# stm_board_f407.net
KiCad netlist of a schematic drawn in EAGLE
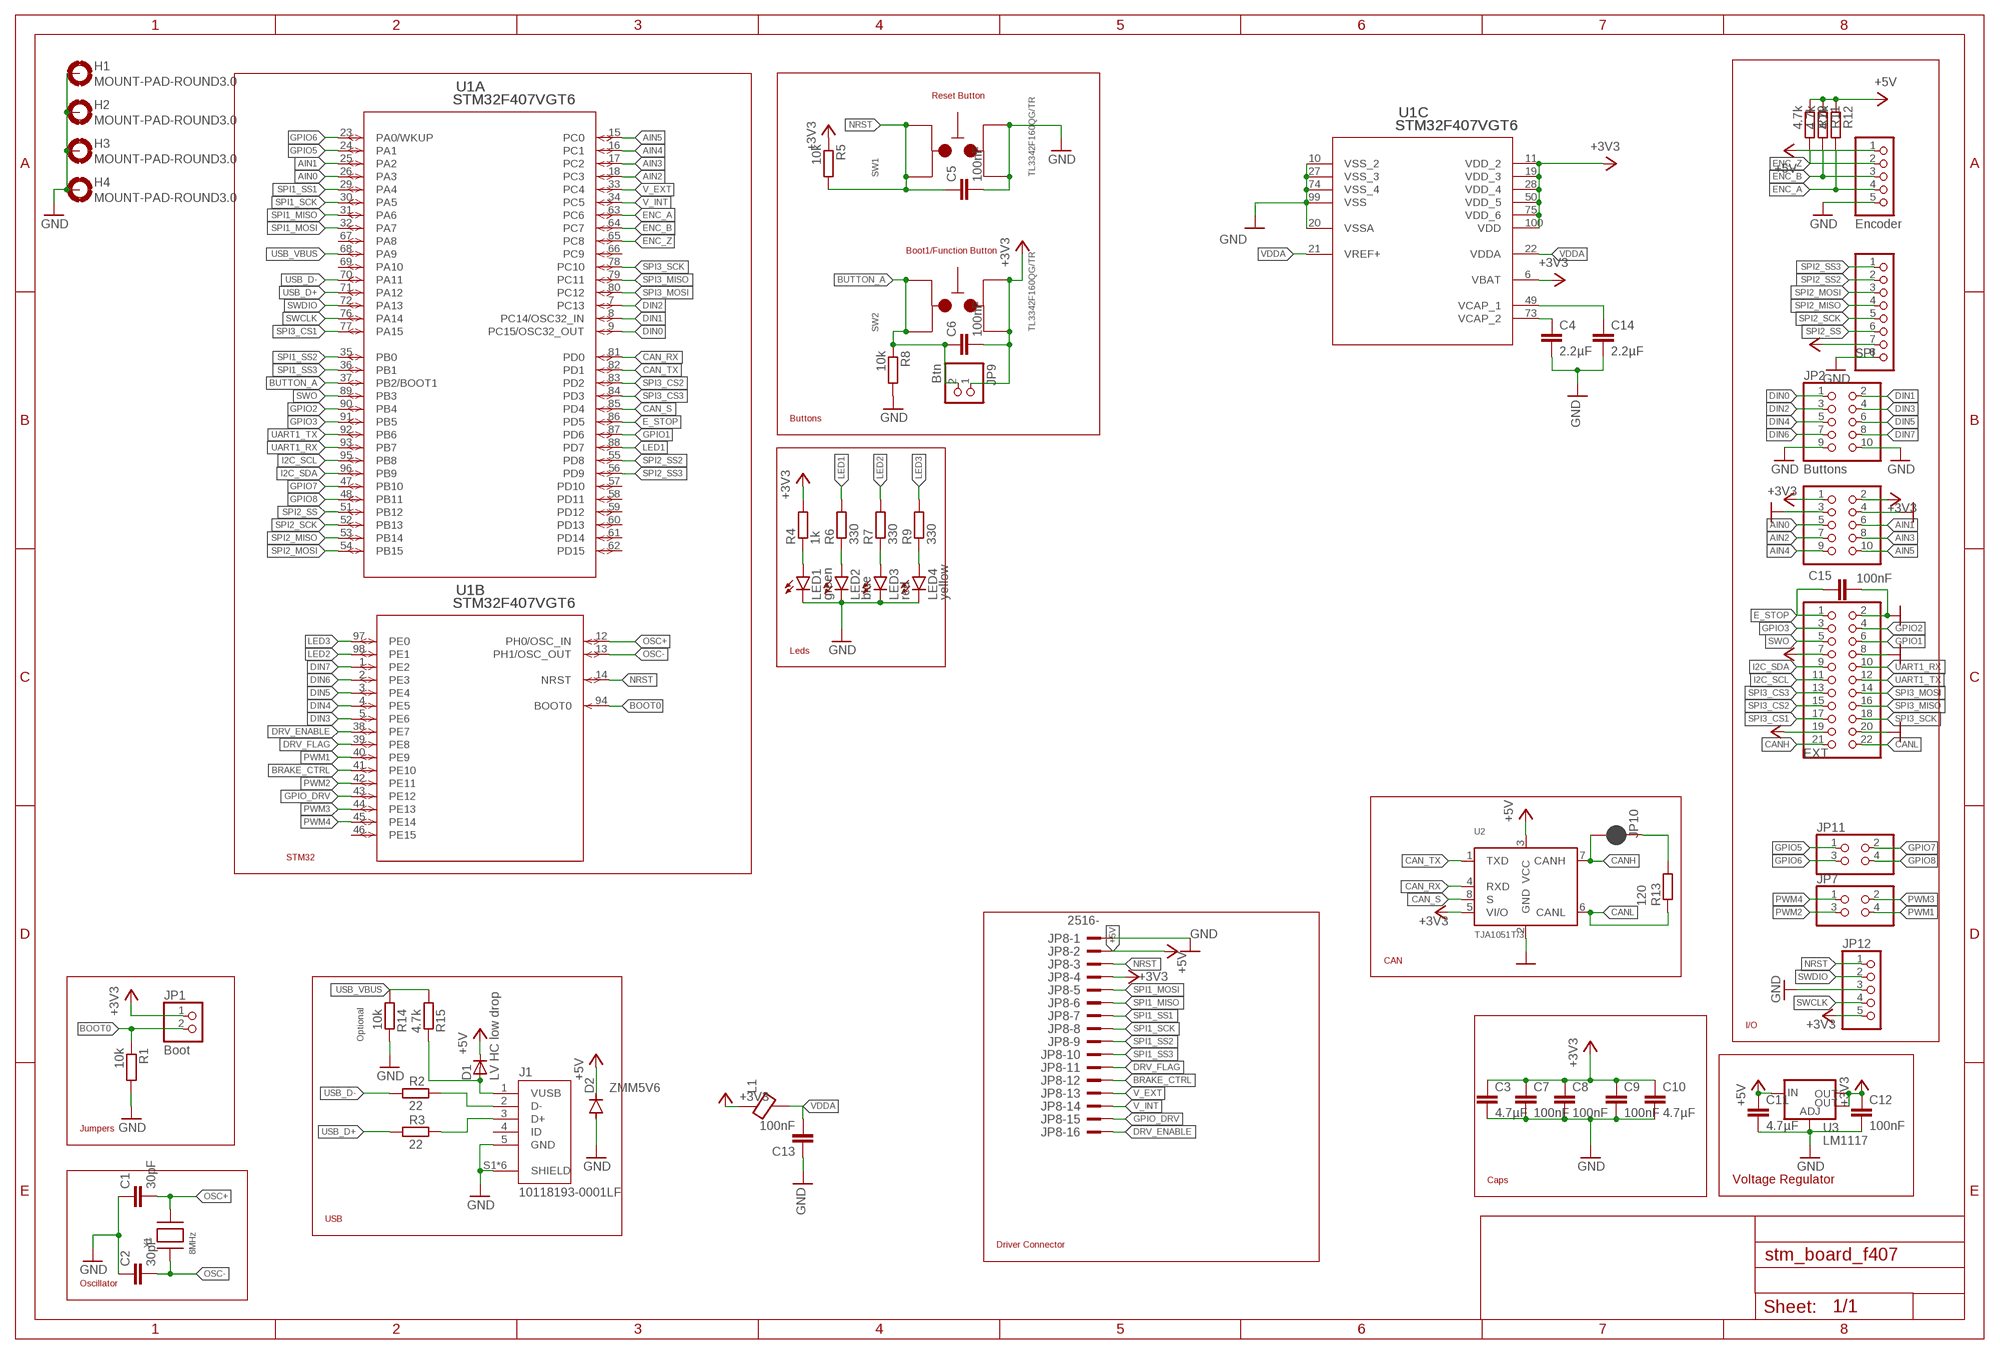
[diagram p0: schematic, sheet 1]

(export (version "E")
  (design (tool "Eeschema 10.0.6"))
  (components
    (comp (ref "C1")
      (value "30pF")
      (footprint "eagle-import:C0603")
      (libsource (lib "eagle-import") (part "C-EUC0603"))
    )
    (comp (ref "C2")
      (value "30pF")
      (footprint "eagle-import:C0603")
      (libsource (lib "eagle-import") (part "C-EUC0603"))
    )
    (comp (ref "C3")
      (value "4.7µF")
      (footprint "eagle-import:C0805")
      (libsource (lib "eagle-import") (part "C-EUC0805"))
    )
    (comp (ref "C4")
      (value "2.2µF")
      (footprint "eagle-import:C0603")
      (libsource (lib "eagle-import") (part "C-EUC0603"))
    )
    (comp (ref "C5")
      (value "100nF")
      (footprint "eagle-import:C0603")
      (libsource (lib "eagle-import") (part "C-EUC0603"))
    )
    (comp (ref "C6")
      (value "100nF")
      (footprint "eagle-import:C0603")
      (libsource (lib "eagle-import") (part "C-EUC0603"))
    )
    (comp (ref "C7")
      (value "100nF")
      (footprint "eagle-import:C0603")
      (libsource (lib "eagle-import") (part "C-EUC0603"))
    )
    (comp (ref "C8")
      (value "100nF")
      (footprint "eagle-import:C0603")
      (libsource (lib "eagle-import") (part "C-EUC0603"))
    )
    (comp (ref "C9")
      (value "100nF")
      (footprint "eagle-import:C0603")
      (libsource (lib "eagle-import") (part "C-EUC0603"))
    )
    (comp (ref "C10")
      (value "4.7µF")
      (footprint "eagle-import:C0805")
      (libsource (lib "eagle-import") (part "C-EUC0805"))
    )
    (comp (ref "C11")
      (value "4.7µF")
      (footprint "eagle-import:C0805")
      (libsource (lib "eagle-import") (part "C-EUC0805"))
    )
    (comp (ref "C12")
      (value "100nF")
      (footprint "eagle-import:C0603")
      (libsource (lib "eagle-import") (part "C-EUC0603"))
    )
    (comp (ref "C13")
      (value "100nF")
      (footprint "eagle-import:C0603")
      (libsource (lib "eagle-import") (part "C-EUC0603"))
    )
    (comp (ref "C14")
      (value "2.2µF")
      (footprint "eagle-import:C0603")
      (libsource (lib "eagle-import") (part "C-EUC0603"))
    )
    (comp (ref "C15")
      (value "100nF")
      (footprint "eagle-import:C0603")
      (libsource (lib "eagle-import") (part "C-EUC0603"))
    )
    (comp (ref "D1")
      (value "LV HC low drop")
      (footprint "eagle-import:SMADIODE")
      (libsource (lib "eagle-import") (part "DIODESMA"))
    )
    (comp (ref "D2")
      (value "ZMM5V6")
      (footprint "eagle-import:MINIMELF")
      (libsource (lib "eagle-import") (part "DIODE-MINIMELF"))
    )
    (comp (ref "H1")
      (value "MOUNT-PAD-ROUND3.0")
      (footprint "eagle-import:3,0-PAD")
      (libsource (lib "eagle-import") (part "MOUNT-PAD-ROUND3.0"))
    )
    (comp (ref "H2")
      (value "MOUNT-PAD-ROUND3.0")
      (footprint "eagle-import:3,0-PAD")
      (libsource (lib "eagle-import") (part "MOUNT-PAD-ROUND3.0"))
    )
    (comp (ref "H3")
      (value "MOUNT-PAD-ROUND3.0")
      (footprint "eagle-import:3,0-PAD")
      (libsource (lib "eagle-import") (part "MOUNT-PAD-ROUND3.0"))
    )
    (comp (ref "H4")
      (value "MOUNT-PAD-ROUND3.0")
      (footprint "eagle-import:3,0-PAD")
      (libsource (lib "eagle-import") (part "MOUNT-PAD-ROUND3.0"))
    )
    (comp (ref "J1")
      (value "10118193-0001LF")
      (footprint "eagle-import:FCI_10118193-0001LF")
      (fields (field (name "MF") "Amphenol ICC"))
      (libsource (lib "eagle-import") (part "10118193-0001LF"))
    )
    (comp (ref "JP1")
      (value "Boot")
      (footprint "eagle-import:1X02")
      (libsource (lib "eagle-import") (part "PINHD-1X2"))
    )
    (comp (ref "JP2")
      (value "Buttons")
      (footprint "eagle-import:2X05")
      (libsource (lib "eagle-import") (part "PINHD-2X5"))
    )
    (comp (ref "JP3")
      (value "Analog")
      (footprint "eagle-import:2X05")
      (libsource (lib "eagle-import") (part "PINHD-2X5"))
    )
    (comp (ref "JP4")
      (value "EXT")
      (footprint "eagle-import:2X11")
      (libsource (lib "eagle-import") (part "PINHD-2X11"))
    )
    (comp (ref "JP5")
      (value "Encoder")
      (footprint "eagle-import:1X05")
      (libsource (lib "eagle-import") (part "PINHD-1X5"))
    )
    (comp (ref "JP6")
      (value "SPI")
      (footprint "eagle-import:1X08")
      (libsource (lib "eagle-import") (part "PINHD-1X8"))
    )
    (comp (ref "JP7")
      (value "PINHD-2X2")
      (footprint "eagle-import:2X02")
      (libsource (lib "eagle-import") (part "PINHD-2X2"))
    )
    (comp (ref "JP8")
      (value "2516-")
      (footprint "eagle-import:PAK100_2500-16")
      (libsource (lib "eagle-import") (part "2516-"))
    )
    (comp (ref "JP9")
      (value "Btn")
      (footprint "eagle-import:1X02")
      (libsource (lib "eagle-import") (part "PINHD-1X2"))
    )
    (comp (ref "JP10")
      (value "JUMPER-SMT_2_NC_PASTE_NO-SILK")
      (footprint "eagle-import:SMT-JUMPER_2_NC_PASTE_NO-SILK")
      (libsource (lib "eagle-import") (part "JUMPER-SMT_2_NC_PASTE_NO-SILK"))
    )
    (comp (ref "JP11")
      (value "PINHD-2X2")
      (footprint "eagle-import:2X02")
      (libsource (lib "eagle-import") (part "PINHD-2X2"))
    )
    (comp (ref "JP12")
      (value "PINHD-1X5")
      (footprint "eagle-import:1X05")
      (libsource (lib "eagle-import") (part "PINHD-1X5"))
    )
    (comp (ref "L1")
      (value "GZ2012D601TF")
      (footprint "eagle-import:BLM21PG331SN1D")
      (fields
        (field (name "DIGIKEY_PART_NUMBER") "490-5988-2-ND")
        (field (name "MANUFACTURER") "Murata Electronics North America")
        (field (name "MPN") "BLM21PG331SN1D")
        (field (name "CREATED_BY") "PCBLayout.com")
      )
      (libsource (lib "eagle-import") (part "BLM21PG331SN1D"))
    )
    (comp (ref "LED1")
      (value "green")
      (footprint "eagle-import:SML0805")
      (libsource (lib "eagle-import") (part "LEDSML0805"))
    )
    (comp (ref "LED2")
      (value "blue")
      (footprint "eagle-import:SML0805")
      (libsource (lib "eagle-import") (part "LEDSML0805"))
    )
    (comp (ref "LED3")
      (value "red")
      (footprint "eagle-import:SML0805")
      (libsource (lib "eagle-import") (part "LEDSML0805"))
    )
    (comp (ref "LED4")
      (value "yellow")
      (footprint "eagle-import:SML0805")
      (libsource (lib "eagle-import") (part "LEDSML0805"))
    )
    (comp (ref "R1")
      (value "10k")
      (footprint "eagle-import:R0603")
      (libsource (lib "eagle-import") (part "R-EU_R0603"))
    )
    (comp (ref "R2")
      (value "22")
      (footprint "eagle-import:R0603")
      (libsource (lib "eagle-import") (part "R-EU_R0603"))
    )
    (comp (ref "R3")
      (value "22")
      (footprint "eagle-import:R0603")
      (libsource (lib "eagle-import") (part "R-EU_R0603"))
    )
    (comp (ref "R4")
      (value "1k")
      (footprint "eagle-import:R0603")
      (libsource (lib "eagle-import") (part "R-EU_R0603"))
    )
    (comp (ref "R5")
      (value "10k")
      (footprint "eagle-import:R0603")
      (libsource (lib "eagle-import") (part "R-EU_R0603"))
    )
    (comp (ref "R6")
      (value "330")
      (footprint "eagle-import:R0603")
      (libsource (lib "eagle-import") (part "R-EU_R0603"))
    )
    (comp (ref "R7")
      (value "330")
      (footprint "eagle-import:R0603")
      (libsource (lib "eagle-import") (part "R-EU_R0603"))
    )
    (comp (ref "R8")
      (value "10k")
      (footprint "eagle-import:R0603")
      (libsource (lib "eagle-import") (part "R-EU_R0603"))
    )
    (comp (ref "R9")
      (value "330")
      (footprint "eagle-import:R0603")
      (libsource (lib "eagle-import") (part "R-EU_R0603"))
    )
    (comp (ref "R10")
      (value "4.7k")
      (footprint "eagle-import:R0603")
      (libsource (lib "eagle-import") (part "R-EU_R0603"))
    )
    (comp (ref "R11")
      (value "4.7k")
      (footprint "eagle-import:R0603")
      (libsource (lib "eagle-import") (part "R-EU_R0603"))
    )
    (comp (ref "R12")
      (value "4.7k")
      (footprint "eagle-import:R0603")
      (libsource (lib "eagle-import") (part "R-EU_R0603"))
    )
    (comp (ref "R13")
      (value "120")
      (footprint "eagle-import:R0603")
      (libsource (lib "eagle-import") (part "R-EU_R0603"))
    )
    (comp (ref "R14")
      (value "10k")
      (footprint "eagle-import:R0603")
      (libsource (lib "eagle-import") (part "R-EU_R0603"))
    )
    (comp (ref "R15")
      (value "4.7k")
      (footprint "eagle-import:R0603")
      (libsource (lib "eagle-import") (part "R-EU_R0603"))
    )
    (comp (ref "SW1")
      (value "TL3342F160QG/TR")
      (footprint "eagle-import:TL3342F160QG_TR")
      (fields
        (field (name "DIGI_KEY_PART_NUMBER") "EG2531CT-ND")
        (field (name "MANUFACTURER") "E-Switch")
        (field (name "CREATED_BY") "PCBLayout.com")
      )
      (libsource (lib "eagle-import") (part "TL3342F160QG/TR"))
    )
    (comp (ref "SW2")
      (value "TL3342F160QG/TR")
      (footprint "eagle-import:TL3342F160QG_TR")
      (fields
        (field (name "DIGI_KEY_PART_NUMBER") "EG2531CT-ND")
        (field (name "MANUFACTURER") "E-Switch")
        (field (name "CREATED_BY") "PCBLayout.com")
      )
      (libsource (lib "eagle-import") (part "TL3342F160QG/TR"))
    )
    (comp (ref "U1")
      (value "STM32F407VGT6")
      (footprint "eagle-import:LQFP100-14X14MM")
      (fields (field (name "COPYRIGHT") "Copyright (C) 2018 Accelerated Designs. All rights reserved"))
      (libsource (lib "eagle-import") (part "STM32F407VGT6"))
    )
    (comp (ref "U2")
      (value "TJA1051T/3")
      (footprint "eagle-import:SOT96-1")
      (fields (field (name "MF") "NXP Semiconductors"))
      (libsource (lib "eagle-import") (part "TJA1051T/3"))
    )
    (comp (ref "U3")
      (value "LM1117")
      (footprint "eagle-import:SOT223")
      (libsource (lib "eagle-import") (part "V_REG_LM1117SOT223"))
    )
    (comp (ref "X1")
      (value "8MHz")
      (footprint "eagle-import:NX5032")
      (libsource (lib "eagle-import") (part "XTALNX5032"))
    )
  )
  (nets
    (net (code "1") (name "+3V3") (class "Default")
      (node (ref "C10") (pin "1") (pinfunction "1_1") (pintype "passive"))
      (node (ref "C12") (pin "1") (pinfunction "1_1") (pintype "passive"))
      (node (ref "C3") (pin "1") (pinfunction "1_1") (pintype "passive"))
      (node (ref "C6") (pin "2") (pinfunction "2_2") (pintype "passive"))
      (node (ref "C7") (pin "1") (pinfunction "1_1") (pintype "passive"))
      (node (ref "C8") (pin "1") (pinfunction "1_1") (pintype "passive"))
      (node (ref "C9") (pin "1") (pinfunction "1_1") (pintype "passive"))
      (node (ref "JP1") (pin "1") (pinfunction "1_1") (pintype "passive"))
      (node (ref "JP12") (pin "5") (pinfunction "5_5") (pintype "passive"))
      (node (ref "JP3") (pin "1") (pinfunction "1_1") (pintype "passive"))
      (node (ref "JP3") (pin "2") (pinfunction "2_2") (pintype "passive"))
      (node (ref "JP4") (pin "7") (pinfunction "7_7") (pintype "passive"))
      (node (ref "JP6") (pin "7") (pinfunction "7_7") (pintype "passive"))
      (node (ref "JP8") (pin "4") (pinfunction "KL_4") (pintype "passive"))
      (node (ref "JP9") (pin "1") (pinfunction "1_1") (pintype "passive"))
      (node (ref "L1") (pin "1") (pinfunction "1_1") (pintype "passive"))
      (node (ref "R4") (pin "2") (pinfunction "2_2") (pintype "passive"))
      (node (ref "R5") (pin "1") (pinfunction "1_1") (pintype "passive"))
      (node (ref "SW2") (pin "1") (pinfunction "1_1") (pintype "passive"))
      (node (ref "SW2") (pin "2") (pinfunction "2_2") (pintype "passive"))
      (node (ref "U1") (pin "100") (pinfunction "VDD_100") (pintype "power_in"))
      (node (ref "U1") (pin "11") (pinfunction "VDD_2_11") (pintype "power_in"))
      (node (ref "U1") (pin "19") (pinfunction "VDD_3_19") (pintype "power_in"))
      (node (ref "U1") (pin "28") (pinfunction "VDD_4_28") (pintype "power_in"))
      (node (ref "U1") (pin "50") (pinfunction "VDD_5_50") (pintype "power_in"))
      (node (ref "U1") (pin "6") (pinfunction "VBAT_6") (pintype "power_in"))
      (node (ref "U1") (pin "75") (pinfunction "VDD_6_75") (pintype "power_in"))
      (node (ref "U2") (pin "5") (pinfunction "VI/O_5") (pintype "passive"))
      (node (ref "U3") (pin "2") (pinfunction "OUT_2") (pintype "output"))
      (node (ref "U3") (pin "4") (pinfunction "OUT_4") (pintype "output"))
    )
    (net (code "2") (name "+5V") (class "Default")
      (node (ref "C11") (pin "1") (pinfunction "1_1") (pintype "passive"))
      (node (ref "D1") (pin "C") (pinfunction "C_C") (pintype "passive"))
      (node (ref "D2") (pin "C") (pinfunction "C_C") (pintype "passive"))
      (node (ref "JP4") (pin "19") (pinfunction "19_19") (pintype "passive"))
      (node (ref "JP5") (pin "1") (pinfunction "1_1") (pintype "passive"))
      (node (ref "JP8") (pin "2") (pinfunction "KL_2") (pintype "passive"))
      (node (ref "R10") (pin "1") (pinfunction "1_1") (pintype "passive"))
      (node (ref "R11") (pin "1") (pinfunction "1_1") (pintype "passive"))
      (node (ref "R12") (pin "1") (pinfunction "1_1") (pintype "passive"))
      (node (ref "U2") (pin "3") (pinfunction "VCC_3") (pintype "bidirectional"))
      (node (ref "U3") (pin "3") (pinfunction "IN_3") (pintype "input"))
    )
    (net (code "3") (name "AIN0") (class "Default")
      (node (ref "JP3") (pin "5") (pinfunction "5_5") (pintype "passive"))
      (node (ref "U1") (pin "26") (pinfunction "PA3_26") (pintype "bidirectional"))
    )
    (net (code "4") (name "AIN1") (class "Default")
      (node (ref "JP3") (pin "6") (pinfunction "6_6") (pintype "passive"))
      (node (ref "U1") (pin "25") (pinfunction "PA2_25") (pintype "bidirectional"))
    )
    (net (code "5") (name "AIN2") (class "Default")
      (node (ref "JP3") (pin "7") (pinfunction "7_7") (pintype "passive"))
      (node (ref "U1") (pin "18") (pinfunction "PC3_18") (pintype "bidirectional"))
    )
    (net (code "6") (name "AIN3") (class "Default")
      (node (ref "JP3") (pin "8") (pinfunction "8_8") (pintype "passive"))
      (node (ref "U1") (pin "17") (pinfunction "PC2_17") (pintype "bidirectional"))
    )
    (net (code "7") (name "AIN4") (class "Default")
      (node (ref "JP3") (pin "9") (pinfunction "9_9") (pintype "passive"))
      (node (ref "U1") (pin "16") (pinfunction "PC1_16") (pintype "bidirectional"))
    )
    (net (code "8") (name "AIN5") (class "Default")
      (node (ref "JP3") (pin "10") (pinfunction "10_10") (pintype "passive"))
      (node (ref "U1") (pin "15") (pinfunction "PC0_15") (pintype "bidirectional"))
    )
    (net (code "9") (name "BOOT0") (class "Default")
      (node (ref "JP1") (pin "2") (pinfunction "2_2") (pintype "passive"))
      (node (ref "R1") (pin "1") (pinfunction "1_1") (pintype "passive"))
      (node (ref "U1") (pin "94") (pinfunction "BOOT0_94") (pintype "input"))
    )
    (net (code "10") (name "BRAKE_CTRL") (class "Default")
      (node (ref "JP8") (pin "12") (pinfunction "KL_12") (pintype "passive"))
      (node (ref "U1") (pin "41") (pinfunction "PE10_41") (pintype "bidirectional"))
    )
    (net (code "11") (name "BUTTON_A") (class "Default")
      (node (ref "C6") (pin "1") (pinfunction "1_1") (pintype "passive"))
      (node (ref "JP9") (pin "2") (pinfunction "2_2") (pintype "passive"))
      (node (ref "R8") (pin "1") (pinfunction "1_1") (pintype "passive"))
      (node (ref "SW2") (pin "3") (pinfunction "3_3") (pintype "passive"))
      (node (ref "SW2") (pin "4") (pinfunction "4_4") (pintype "passive"))
      (node (ref "U1") (pin "37") (pinfunction "PB2/BOOT1_37") (pintype "bidirectional"))
    )
    (net (code "12") (name "CANH") (class "Default")
      (node (ref "JP10") (pin "2") (pinfunction "2_2") (pintype "passive"))
      (node (ref "JP4") (pin "21") (pinfunction "21_21") (pintype "passive"))
      (node (ref "U2") (pin "7") (pinfunction "CANH_7") (pintype "bidirectional"))
    )
    (net (code "13") (name "CANL") (class "Default")
      (node (ref "JP4") (pin "22") (pinfunction "22_22") (pintype "passive"))
      (node (ref "R13") (pin "1") (pinfunction "1_1") (pintype "passive"))
      (node (ref "U2") (pin "6") (pinfunction "CANL_6") (pintype "bidirectional"))
    )
    (net (code "14") (name "CAN_RX") (class "Default")
      (node (ref "U1") (pin "81") (pinfunction "PD0_81") (pintype "bidirectional"))
      (node (ref "U2") (pin "4") (pinfunction "RXD_4") (pintype "bidirectional"))
    )
    (net (code "15") (name "CAN_S") (class "Default")
      (node (ref "U1") (pin "85") (pinfunction "PD4_85") (pintype "bidirectional"))
      (node (ref "U2") (pin "8") (pinfunction "S_8") (pintype "power_in"))
    )
    (net (code "16") (name "CAN_TX") (class "Default")
      (node (ref "U1") (pin "82") (pinfunction "PD1_82") (pintype "bidirectional"))
      (node (ref "U2") (pin "1") (pinfunction "TXD_1") (pintype "output"))
    )
    (net (code "17") (name "DIN0") (class "Default")
      (node (ref "JP2") (pin "1") (pinfunction "1_1") (pintype "passive"))
      (node (ref "U1") (pin "9") (pinfunction "PC15/OSC32_OUT_9") (pintype "bidirectional"))
    )
    (net (code "18") (name "DIN1") (class "Default")
      (node (ref "JP2") (pin "2") (pinfunction "2_2") (pintype "passive"))
      (node (ref "U1") (pin "8") (pinfunction "PC14/OSC32_IN_8") (pintype "bidirectional"))
    )
    (net (code "19") (name "DIN2") (class "Default")
      (node (ref "JP2") (pin "3") (pinfunction "3_3") (pintype "passive"))
      (node (ref "U1") (pin "7") (pinfunction "PC13_7") (pintype "bidirectional"))
    )
    (net (code "20") (name "DIN3") (class "Default")
      (node (ref "JP2") (pin "4") (pinfunction "4_4") (pintype "passive"))
      (node (ref "U1") (pin "5") (pinfunction "PE6_5") (pintype "bidirectional"))
    )
    (net (code "21") (name "DIN4") (class "Default")
      (node (ref "JP2") (pin "5") (pinfunction "5_5") (pintype "passive"))
      (node (ref "U1") (pin "4") (pinfunction "PE5_4") (pintype "bidirectional"))
    )
    (net (code "22") (name "DIN5") (class "Default")
      (node (ref "JP2") (pin "6") (pinfunction "6_6") (pintype "passive"))
      (node (ref "U1") (pin "3") (pinfunction "PE4_3") (pintype "bidirectional"))
    )
    (net (code "23") (name "DIN6") (class "Default")
      (node (ref "JP2") (pin "7") (pinfunction "7_7") (pintype "passive"))
      (node (ref "U1") (pin "2") (pinfunction "PE3_2") (pintype "bidirectional"))
    )
    (net (code "24") (name "DIN7") (class "Default")
      (node (ref "JP2") (pin "8") (pinfunction "8_8") (pintype "passive"))
      (node (ref "U1") (pin "1") (pinfunction "PE2_1") (pintype "bidirectional"))
    )
    (net (code "25") (name "DRV_ENABLE") (class "Default")
      (node (ref "JP8") (pin "16") (pinfunction "KL_16") (pintype "passive"))
      (node (ref "U1") (pin "38") (pinfunction "PE7_38") (pintype "bidirectional"))
    )
    (net (code "26") (name "DRV_FLAG") (class "Default")
      (node (ref "JP8") (pin "11") (pinfunction "KL_11") (pintype "passive"))
      (node (ref "U1") (pin "39") (pinfunction "PE8_39") (pintype "bidirectional"))
    )
    (net (code "27") (name "ENC_A") (class "Default")
      (node (ref "JP5") (pin "4") (pinfunction "4_4") (pintype "passive"))
      (node (ref "R12") (pin "2") (pinfunction "2_2") (pintype "passive"))
      (node (ref "U1") (pin "63") (pinfunction "PC6_63") (pintype "bidirectional"))
    )
    (net (code "28") (name "ENC_B") (class "Default")
      (node (ref "JP5") (pin "3") (pinfunction "3_3") (pintype "passive"))
      (node (ref "R11") (pin "2") (pinfunction "2_2") (pintype "passive"))
      (node (ref "U1") (pin "64") (pinfunction "PC7_64") (pintype "bidirectional"))
    )
    (net (code "29") (name "ENC_Z") (class "Default")
      (node (ref "JP5") (pin "2") (pinfunction "2_2") (pintype "passive"))
      (node (ref "R10") (pin "2") (pinfunction "2_2") (pintype "passive"))
      (node (ref "U1") (pin "65") (pinfunction "PC8_65") (pintype "bidirectional"))
    )
    (net (code "30") (name "E_STOP") (class "Default")
      (node (ref "C15") (pin "1") (pinfunction "1_1") (pintype "passive"))
      (node (ref "JP4") (pin "1") (pinfunction "1_1") (pintype "passive"))
      (node (ref "U1") (pin "86") (pinfunction "PD5_86") (pintype "bidirectional"))
    )
    (net (code "31") (name "GND") (class "Default")
      (node (ref "C1") (pin "1") (pinfunction "1_1") (pintype "passive"))
      (node (ref "C10") (pin "2") (pinfunction "2_2") (pintype "passive"))
      (node (ref "C11") (pin "2") (pinfunction "2_2") (pintype "passive"))
      (node (ref "C12") (pin "2") (pinfunction "2_2") (pintype "passive"))
      (node (ref "C13") (pin "1") (pinfunction "1_1") (pintype "passive"))
      (node (ref "C14") (pin "2") (pinfunction "2_2") (pintype "passive"))
      (node (ref "C15") (pin "2") (pinfunction "2_2") (pintype "passive"))
      (node (ref "C2") (pin "1") (pinfunction "1_1") (pintype "passive"))
      (node (ref "C3") (pin "2") (pinfunction "2_2") (pintype "passive"))
      (node (ref "C4") (pin "2") (pinfunction "2_2") (pintype "passive"))
      (node (ref "C5") (pin "2") (pinfunction "2_2") (pintype "passive"))
      (node (ref "C7") (pin "2") (pinfunction "2_2") (pintype "passive"))
      (node (ref "C8") (pin "2") (pinfunction "2_2") (pintype "passive"))
      (node (ref "C9") (pin "2") (pinfunction "2_2") (pintype "passive"))
      (node (ref "D2") (pin "A") (pinfunction "A_A") (pintype "passive"))
      (node (ref "H1") (pin "B3,0") (pinfunction "MOUNT_B3,0") (pintype "passive"))
      (node (ref "H2") (pin "B3,0") (pinfunction "MOUNT_B3,0") (pintype "passive"))
      (node (ref "H3") (pin "B3,0") (pinfunction "MOUNT_B3,0") (pintype "passive"))
      (node (ref "H4") (pin "B3,0") (pinfunction "MOUNT_B3,0") (pintype "passive"))
      (node (ref "J1") (pin "5") (pinfunction "GND_5") (pintype "passive"))
      (node (ref "J1") (pin "S1") (pinfunction "SHIELD_S1") (pintype "passive"))
      (node (ref "J1") (pin "S2") (pinfunction "SHIELD_S2") (pintype "passive"))
      (node (ref "J1") (pin "S3") (pinfunction "SHIELD_S3") (pintype "passive"))
      (node (ref "J1") (pin "S4") (pinfunction "SHIELD_S4") (pintype "passive"))
      (node (ref "J1") (pin "S5") (pinfunction "SHIELD_S5") (pintype "passive"))
      (node (ref "J1") (pin "S6") (pinfunction "SHIELD_S6") (pintype "passive"))
      (node (ref "JP12") (pin "3") (pinfunction "3_3") (pintype "passive"))
      (node (ref "JP2") (pin "10") (pinfunction "10_10") (pintype "passive"))
      (node (ref "JP2") (pin "9") (pinfunction "9_9") (pintype "passive"))
      (node (ref "JP3") (pin "3") (pinfunction "3_3") (pintype "passive"))
      (node (ref "JP3") (pin "4") (pinfunction "4_4") (pintype "passive"))
      (node (ref "JP4") (pin "2") (pinfunction "2_2") (pintype "passive"))
      (node (ref "JP4") (pin "20") (pinfunction "20_20") (pintype "passive"))
      (node (ref "JP4") (pin "8") (pinfunction "8_8") (pintype "passive"))
      (node (ref "JP5") (pin "5") (pinfunction "5_5") (pintype "passive"))
      (node (ref "JP6") (pin "8") (pinfunction "8_8") (pintype "passive"))
      (node (ref "JP8") (pin "1") (pinfunction "KL_1") (pintype "passive"))
      (node (ref "LED1") (pin "C") (pinfunction "C_C") (pintype "passive"))
      (node (ref "LED2") (pin "C") (pinfunction "C_C") (pintype "passive"))
      (node (ref "LED3") (pin "C") (pinfunction "C_C") (pintype "passive"))
      (node (ref "LED4") (pin "C") (pinfunction "C_C") (pintype "passive"))
      (node (ref "R1") (pin "2") (pinfunction "2_2") (pintype "passive"))
      (node (ref "R14") (pin "2") (pinfunction "2_2") (pintype "passive"))
      (node (ref "R8") (pin "2") (pinfunction "2_2") (pintype "passive"))
      (node (ref "SW1") (pin "1") (pinfunction "1_1") (pintype "passive"))
      (node (ref "SW1") (pin "2") (pinfunction "2_2") (pintype "passive"))
      (node (ref "U1") (pin "10") (pinfunction "VSS_2_10") (pintype "power_in"))
      (node (ref "U1") (pin "20") (pinfunction "VSSA_20") (pintype "power_in"))
      (node (ref "U1") (pin "27") (pinfunction "VSS_3_27") (pintype "power_in"))
      (node (ref "U1") (pin "74") (pinfunction "VSS_4_74") (pintype "power_in"))
      (node (ref "U1") (pin "99") (pinfunction "VSS_99") (pintype "power_in"))
      (node (ref "U2") (pin "2") (pinfunction "GND_2") (pintype "bidirectional"))
      (node (ref "U3") (pin "1") (pinfunction "ADJ_1") (pintype "input"))
    )
    (net (code "32") (name "GPIO1") (class "Default")
      (node (ref "JP4") (pin "6") (pinfunction "6_6") (pintype "passive"))
      (node (ref "U1") (pin "87") (pinfunction "PD6_87") (pintype "bidirectional"))
    )
    (net (code "33") (name "GPIO2") (class "Default")
      (node (ref "JP4") (pin "4") (pinfunction "4_4") (pintype "passive"))
      (node (ref "U1") (pin "90") (pinfunction "PB4_90") (pintype "bidirectional"))
    )
    (net (code "34") (name "GPIO3") (class "Default")
      (node (ref "JP4") (pin "3") (pinfunction "3_3") (pintype "passive"))
      (node (ref "U1") (pin "91") (pinfunction "PB5_91") (pintype "bidirectional"))
    )
    (net (code "35") (name "GPIO5") (class "Default")
      (node (ref "JP11") (pin "1") (pinfunction "1_1") (pintype "passive"))
      (node (ref "U1") (pin "24") (pinfunction "PA1_24") (pintype "bidirectional"))
    )
    (net (code "36") (name "GPIO6") (class "Default")
      (node (ref "JP11") (pin "3") (pinfunction "3_3") (pintype "passive"))
      (node (ref "U1") (pin "23") (pinfunction "PA0/WKUP_23") (pintype "bidirectional"))
    )
    (net (code "37") (name "GPIO7") (class "Default")
      (node (ref "JP11") (pin "2") (pinfunction "2_2") (pintype "passive"))
      (node (ref "U1") (pin "47") (pinfunction "PB10_47") (pintype "bidirectional"))
    )
    (net (code "38") (name "GPIO8") (class "Default")
      (node (ref "JP11") (pin "4") (pinfunction "4_4") (pintype "passive"))
      (node (ref "U1") (pin "48") (pinfunction "PB11_48") (pintype "bidirectional"))
    )
    (net (code "39") (name "GPIO_DRV") (class "Default")
      (node (ref "JP8") (pin "15") (pinfunction "KL_15") (pintype "passive"))
      (node (ref "U1") (pin "43") (pinfunction "PE12_43") (pintype "bidirectional"))
    )
    (net (code "40") (name "I2C_SCL") (class "Default")
      (node (ref "JP4") (pin "11") (pinfunction "11_11") (pintype "passive"))
      (node (ref "U1") (pin "95") (pinfunction "PB8_95") (pintype "bidirectional"))
    )
    (net (code "41") (name "I2C_SDA") (class "Default")
      (node (ref "JP4") (pin "9") (pinfunction "9_9") (pintype "passive"))
      (node (ref "U1") (pin "96") (pinfunction "PB9_96") (pintype "bidirectional"))
    )
    (net (code "42") (name "LED1") (class "Default")
      (node (ref "R6") (pin "2") (pinfunction "2_2") (pintype "passive"))
      (node (ref "U1") (pin "88") (pinfunction "PD7_88") (pintype "bidirectional"))
    )
    (net (code "43") (name "LED2") (class "Default")
      (node (ref "R7") (pin "2") (pinfunction "2_2") (pintype "passive"))
      (node (ref "U1") (pin "98") (pinfunction "PE1_98") (pintype "bidirectional"))
    )
    (net (code "44") (name "LED3") (class "Default")
      (node (ref "R9") (pin "2") (pinfunction "2_2") (pintype "passive"))
      (node (ref "U1") (pin "97") (pinfunction "PE0_97") (pintype "bidirectional"))
    )
    (net (code "45") (name "NRST") (class "Default")
      (node (ref "C5") (pin "1") (pinfunction "1_1") (pintype "passive"))
      (node (ref "JP12") (pin "1") (pinfunction "1_1") (pintype "passive"))
      (node (ref "JP8") (pin "3") (pinfunction "KL_3") (pintype "passive"))
      (node (ref "R5") (pin "2") (pinfunction "2_2") (pintype "passive"))
      (node (ref "SW1") (pin "3") (pinfunction "3_3") (pintype "passive"))
      (node (ref "SW1") (pin "4") (pinfunction "4_4") (pintype "passive"))
      (node (ref "U1") (pin "14") (pinfunction "NRST_14") (pintype "bidirectional"))
    )
    (net (code "46") (name "Net-(J1-D+)") (class "Default")
      (node (ref "J1") (pin "3") (pinfunction "D+_3") (pintype "passive"))
      (node (ref "R3") (pin "2") (pinfunction "2_2") (pintype "passive"))
    )
    (net (code "47") (name "Net-(J1-D-)") (class "Default")
      (node (ref "J1") (pin "2") (pinfunction "D-_2") (pintype "passive"))
      (node (ref "R2") (pin "2") (pinfunction "2_2") (pintype "passive"))
    )
    (net (code "48") (name "Net-(J1-VUSB)") (class "Default")
      (node (ref "D1") (pin "A") (pinfunction "A_A") (pintype "passive"))
      (node (ref "J1") (pin "1") (pinfunction "VUSB_1") (pintype "passive"))
      (node (ref "R15") (pin "2") (pinfunction "2_2") (pintype "passive"))
    )
    (net (code "49") (name "Net-(JP10-Pad1)") (class "Default")
      (node (ref "JP10") (pin "1") (pinfunction "1_1") (pintype "passive"))
      (node (ref "R13") (pin "2") (pinfunction "2_2") (pintype "passive"))
    )
    (net (code "50") (name "Net-(LED1-PadA)") (class "Default")
      (node (ref "LED1") (pin "A") (pinfunction "A_A") (pintype "passive"))
      (node (ref "R4") (pin "1") (pinfunction "1_1") (pintype "passive"))
    )
    (net (code "51") (name "Net-(LED2-PadA)") (class "Default")
      (node (ref "LED2") (pin "A") (pinfunction "A_A") (pintype "passive"))
      (node (ref "R6") (pin "1") (pinfunction "1_1") (pintype "passive"))
    )
    (net (code "52") (name "Net-(LED3-PadA)") (class "Default")
      (node (ref "LED3") (pin "A") (pinfunction "A_A") (pintype "passive"))
      (node (ref "R7") (pin "1") (pinfunction "1_1") (pintype "passive"))
    )
    (net (code "53") (name "Net-(LED4-PadA)") (class "Default")
      (node (ref "LED4") (pin "A") (pinfunction "A_A") (pintype "passive"))
      (node (ref "R9") (pin "1") (pinfunction "1_1") (pintype "passive"))
    )
    (net (code "54") (name "Net-(U1C-VCAP_1)") (class "Default")
      (node (ref "C14") (pin "1") (pinfunction "1_1") (pintype "passive"))
      (node (ref "U1") (pin "49") (pinfunction "VCAP_1_49") (pintype "power_in"))
    )
    (net (code "55") (name "Net-(U1C-VCAP_2)") (class "Default")
      (node (ref "C4") (pin "1") (pinfunction "1_1") (pintype "passive"))
      (node (ref "U1") (pin "73") (pinfunction "VCAP_2_73") (pintype "power_in"))
    )
    (net (code "56") (name "OSC+") (class "Default")
      (node (ref "C1") (pin "2") (pinfunction "2_2") (pintype "passive"))
      (node (ref "U1") (pin "12") (pinfunction "PH0/OSC_IN_12") (pintype "bidirectional"))
      (node (ref "X1") (pin "P$2") (pinfunction "P$2_P$2") (pintype "bidirectional"))
    )
    (net (code "57") (name "OSC-") (class "Default")
      (node (ref "C2") (pin "2") (pinfunction "2_2") (pintype "passive"))
      (node (ref "U1") (pin "13") (pinfunction "PH1/OSC_OUT_13") (pintype "bidirectional"))
      (node (ref "X1") (pin "P$1") (pinfunction "P$1_P$1") (pintype "bidirectional"))
    )
    (net (code "58") (name "PWM1") (class "Default")
      (node (ref "JP7") (pin "4") (pinfunction "4_4") (pintype "passive"))
      (node (ref "U1") (pin "40") (pinfunction "PE9_40") (pintype "bidirectional"))
    )
    (net (code "59") (name "PWM2") (class "Default")
      (node (ref "JP7") (pin "3") (pinfunction "3_3") (pintype "passive"))
      (node (ref "U1") (pin "42") (pinfunction "PE11_42") (pintype "bidirectional"))
    )
    (net (code "60") (name "PWM3") (class "Default")
      (node (ref "JP7") (pin "2") (pinfunction "2_2") (pintype "passive"))
      (node (ref "U1") (pin "44") (pinfunction "PE13_44") (pintype "bidirectional"))
    )
    (net (code "61") (name "PWM4") (class "Default")
      (node (ref "JP7") (pin "1") (pinfunction "1_1") (pintype "passive"))
      (node (ref "U1") (pin "45") (pinfunction "PE14_45") (pintype "bidirectional"))
    )
    (net (code "62") (name "SPI1_MISO") (class "Default")
      (node (ref "JP8") (pin "6") (pinfunction "KL_6") (pintype "passive"))
      (node (ref "U1") (pin "31") (pinfunction "PA6_31") (pintype "bidirectional"))
    )
    (net (code "63") (name "SPI1_MOSI") (class "Default")
      (node (ref "JP8") (pin "5") (pinfunction "KL_5") (pintype "passive"))
      (node (ref "U1") (pin "32") (pinfunction "PA7_32") (pintype "bidirectional"))
    )
    (net (code "64") (name "SPI1_SCK") (class "Default")
      (node (ref "JP8") (pin "8") (pinfunction "KL_8") (pintype "passive"))
      (node (ref "U1") (pin "30") (pinfunction "PA5_30") (pintype "bidirectional"))
    )
    (net (code "65") (name "SPI1_SS1") (class "Default")
      (node (ref "JP8") (pin "7") (pinfunction "KL_7") (pintype "passive"))
      (node (ref "U1") (pin "29") (pinfunction "PA4_29") (pintype "bidirectional"))
    )
    (net (code "66") (name "SPI1_SS2") (class "Default")
      (node (ref "JP8") (pin "9") (pinfunction "KL_9") (pintype "passive"))
      (node (ref "U1") (pin "35") (pinfunction "PB0_35") (pintype "bidirectional"))
    )
    (net (code "67") (name "SPI1_SS3") (class "Default")
      (node (ref "JP8") (pin "10") (pinfunction "KL_10") (pintype "passive"))
      (node (ref "U1") (pin "36") (pinfunction "PB1_36") (pintype "bidirectional"))
    )
    (net (code "68") (name "SPI2_MISO") (class "Default")
      (node (ref "JP6") (pin "4") (pinfunction "4_4") (pintype "passive"))
      (node (ref "U1") (pin "53") (pinfunction "PB14_53") (pintype "bidirectional"))
    )
    (net (code "69") (name "SPI2_MOSI") (class "Default")
      (node (ref "JP6") (pin "3") (pinfunction "3_3") (pintype "passive"))
      (node (ref "U1") (pin "54") (pinfunction "PB15_54") (pintype "bidirectional"))
    )
    (net (code "70") (name "SPI2_SCK") (class "Default")
      (node (ref "JP6") (pin "5") (pinfunction "5_5") (pintype "passive"))
      (node (ref "U1") (pin "52") (pinfunction "PB13_52") (pintype "bidirectional"))
    )
    (net (code "71") (name "SPI2_SS") (class "Default")
      (node (ref "JP6") (pin "6") (pinfunction "6_6") (pintype "passive"))
      (node (ref "U1") (pin "51") (pinfunction "PB12_51") (pintype "bidirectional"))
    )
    (net (code "72") (name "SPI2_SS2") (class "Default")
      (node (ref "JP6") (pin "2") (pinfunction "2_2") (pintype "passive"))
      (node (ref "U1") (pin "55") (pinfunction "PD8_55") (pintype "bidirectional"))
    )
    (net (code "73") (name "SPI2_SS3") (class "Default")
      (node (ref "JP6") (pin "1") (pinfunction "1_1") (pintype "passive"))
      (node (ref "U1") (pin "56") (pinfunction "PD9_56") (pintype "bidirectional"))
    )
    (net (code "74") (name "SPI3_CS1") (class "Default")
      (node (ref "JP4") (pin "17") (pinfunction "17_17") (pintype "passive"))
      (node (ref "U1") (pin "77") (pinfunction "PA15_77") (pintype "bidirectional"))
    )
    (net (code "75") (name "SPI3_CS2") (class "Default")
      (node (ref "JP4") (pin "15") (pinfunction "15_15") (pintype "passive"))
      (node (ref "U1") (pin "83") (pinfunction "PD2_83") (pintype "bidirectional"))
    )
    (net (code "76") (name "SPI3_CS3") (class "Default")
      (node (ref "JP4") (pin "13") (pinfunction "13_13") (pintype "passive"))
      (node (ref "U1") (pin "84") (pinfunction "PD3_84") (pintype "bidirectional"))
    )
    (net (code "77") (name "SPI3_MISO") (class "Default")
      (node (ref "JP4") (pin "16") (pinfunction "16_16") (pintype "passive"))
      (node (ref "U1") (pin "79") (pinfunction "PC11_79") (pintype "bidirectional"))
    )
    (net (code "78") (name "SPI3_MOSI") (class "Default")
      (node (ref "JP4") (pin "14") (pinfunction "14_14") (pintype "passive"))
      (node (ref "U1") (pin "80") (pinfunction "PC12_80") (pintype "bidirectional"))
    )
    (net (code "79") (name "SPI3_SCK") (class "Default")
      (node (ref "JP4") (pin "18") (pinfunction "18_18") (pintype "passive"))
      (node (ref "U1") (pin "78") (pinfunction "PC10_78") (pintype "bidirectional"))
    )
    (net (code "80") (name "SWCLK") (class "Default")
      (node (ref "JP12") (pin "4") (pinfunction "4_4") (pintype "passive"))
      (node (ref "U1") (pin "76") (pinfunction "PA14_76") (pintype "bidirectional"))
    )
    (net (code "81") (name "SWDIO") (class "Default")
      (node (ref "JP12") (pin "2") (pinfunction "2_2") (pintype "passive"))
      (node (ref "U1") (pin "72") (pinfunction "PA13_72") (pintype "bidirectional"))
    )
    (net (code "82") (name "SWO") (class "Default")
      (node (ref "JP4") (pin "5") (pinfunction "5_5") (pintype "passive"))
      (node (ref "U1") (pin "89") (pinfunction "PB3_89") (pintype "bidirectional"))
    )
    (net (code "83") (name "UART1_RX") (class "Default")
      (node (ref "JP4") (pin "10") (pinfunction "10_10") (pintype "passive"))
      (node (ref "U1") (pin "93") (pinfunction "PB7_93") (pintype "bidirectional"))
    )
    (net (code "84") (name "UART1_TX") (class "Default")
      (node (ref "JP4") (pin "12") (pinfunction "12_12") (pintype "passive"))
      (node (ref "U1") (pin "92") (pinfunction "PB6_92") (pintype "bidirectional"))
    )
    (net (code "85") (name "USB_D+") (class "Default")
      (node (ref "R3") (pin "1") (pinfunction "1_1") (pintype "passive"))
      (node (ref "U1") (pin "71") (pinfunction "PA12_71") (pintype "bidirectional"))
    )
    (net (code "86") (name "USB_D-") (class "Default")
      (node (ref "R2") (pin "1") (pinfunction "1_1") (pintype "passive"))
      (node (ref "U1") (pin "70") (pinfunction "PA11_70") (pintype "bidirectional"))
    )
    (net (code "87") (name "USB_VBUS") (class "Default")
      (node (ref "R14") (pin "1") (pinfunction "1_1") (pintype "passive"))
      (node (ref "R15") (pin "1") (pinfunction "1_1") (pintype "passive"))
      (node (ref "U1") (pin "68") (pinfunction "PA9_68") (pintype "bidirectional"))
    )
    (net (code "88") (name "VDDA") (class "Default")
      (node (ref "C13") (pin "2") (pinfunction "2_2") (pintype "passive"))
      (node (ref "L1") (pin "2") (pinfunction "2_2") (pintype "passive"))
      (node (ref "U1") (pin "21") (pinfunction "VREF+_21") (pintype "power_in"))
      (node (ref "U1") (pin "22") (pinfunction "VDDA_22") (pintype "power_in"))
    )
    (net (code "89") (name "V_EXT") (class "Default")
      (node (ref "JP8") (pin "13") (pinfunction "KL_13") (pintype "passive"))
      (node (ref "U1") (pin "33") (pinfunction "PC4_33") (pintype "bidirectional"))
    )
    (net (code "90") (name "V_INT") (class "Default")
      (node (ref "JP8") (pin "14") (pinfunction "KL_14") (pintype "passive"))
      (node (ref "U1") (pin "34") (pinfunction "PC5_34") (pintype "bidirectional"))
    )
    (net (code "91") (name "unconnected-(J1-ID-Pad4)") (class "Default")
      (node (ref "J1") (pin "4") (pinfunction "ID_4") (pintype "passive"))
    )
    (net (code "92") (name "unconnected-(U1A-PA8-Pad67)") (class "Default")
      (node (ref "U1") (pin "67") (pinfunction "PA8_67") (pintype "bidirectional"))
    )
    (net (code "93") (name "unconnected-(U1A-PA10-Pad69)") (class "Default")
      (node (ref "U1") (pin "69") (pinfunction "PA10_69") (pintype "bidirectional"))
    )
    (net (code "94") (name "unconnected-(U1A-PC9-Pad66)") (class "Default")
      (node (ref "U1") (pin "66") (pinfunction "PC9_66") (pintype "bidirectional"))
    )
    (net (code "95") (name "unconnected-(U1A-PD10-Pad57)") (class "Default")
      (node (ref "U1") (pin "57") (pinfunction "PD10_57") (pintype "bidirectional"))
    )
    (net (code "96") (name "unconnected-(U1A-PD11-Pad58)") (class "Default")
      (node (ref "U1") (pin "58") (pinfunction "PD11_58") (pintype "bidirectional"))
    )
    (net (code "97") (name "unconnected-(U1A-PD12-Pad59)") (class "Default")
      (node (ref "U1") (pin "59") (pinfunction "PD12_59") (pintype "bidirectional"))
    )
    (net (code "98") (name "unconnected-(U1A-PD13-Pad60)") (class "Default")
      (node (ref "U1") (pin "60") (pinfunction "PD13_60") (pintype "bidirectional"))
    )
    (net (code "99") (name "unconnected-(U1A-PD14-Pad61)") (class "Default")
      (node (ref "U1") (pin "61") (pinfunction "PD14_61") (pintype "bidirectional"))
    )
    (net (code "100") (name "unconnected-(U1A-PD15-Pad62)") (class "Default")
      (node (ref "U1") (pin "62") (pinfunction "PD15_62") (pintype "bidirectional"))
    )
    (net (code "101") (name "unconnected-(U1B-PE15-Pad46)") (class "Default")
      (node (ref "U1") (pin "46") (pinfunction "PE15_46") (pintype "bidirectional"))
    )
  )
)
